# starfox.net
KiCad netlist of a schematic drawn in EAGLE
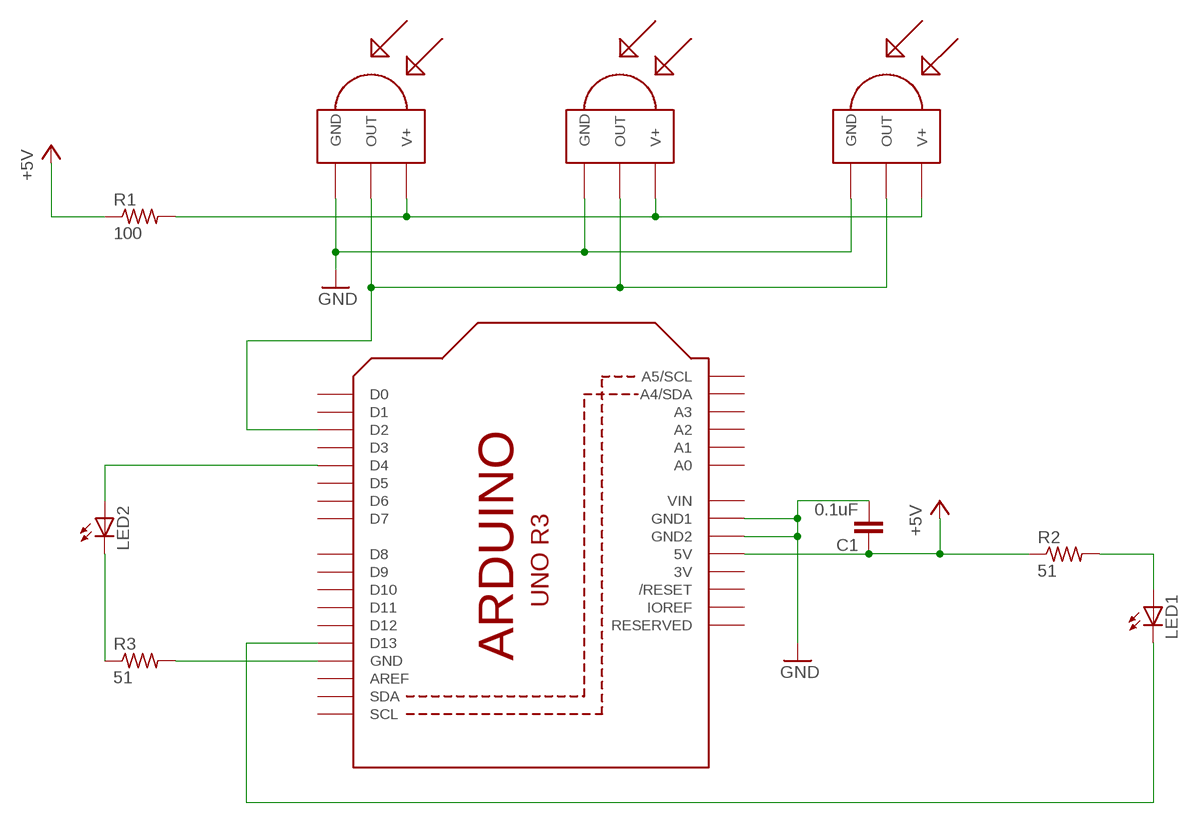
[diagram p0: schematic, sheet 1]

(export (version "E")
  (design (tool "Eeschema 10.0.6"))
  (components
    (comp (ref "C1")
      (value "0.1uF")
      (footprint "eagle-import:C025-025X050")
      (libsource (lib "eagle-import") (part "C-EU025-025X050"))
    )
    (comp (ref "LED1")
      (value "LED5MM")
      (footprint "eagle-import:LED5MM")
      (libsource (lib "eagle-import") (part "LED5MM"))
    )
    (comp (ref "LED2")
      (value "LED5MM")
      (footprint "eagle-import:LED5MM")
      (libsource (lib "eagle-import") (part "LED5MM"))
    )
    (comp (ref "R1")
      (value "100")
      (footprint "eagle-import:0204_7")
      (libsource (lib "eagle-import") (part "R-US_0204/7"))
    )
    (comp (ref "R2")
      (value "51")
      (footprint "eagle-import:0204_7")
      (libsource (lib "eagle-import") (part "R-US_0204/7"))
    )
    (comp (ref "R3")
      (value "51")
      (footprint "eagle-import:0204_7")
      (libsource (lib "eagle-import") (part "R-US_0204/7"))
    )
    (comp (ref "U$1")
      (value "TSOP4836")
      (footprint "eagle-import:TSOP18XX")
      (libsource (lib "eagle-import") (part "TSOP4836"))
    )
    (comp (ref "U$2")
      (value "TSOP4836")
      (footprint "eagle-import:TSOP18XX")
      (libsource (lib "eagle-import") (part "TSOP4836"))
    )
    (comp (ref "U$3")
      (value "TSOP4836")
      (footprint "eagle-import:TSOP18XX")
      (libsource (lib "eagle-import") (part "TSOP4836"))
    )
    (comp (ref "U1")
      (value "ARDUINOR3-DIMENSION")
      (footprint "eagle-import:ARDUINOR3")
      (libsource (lib "eagle-import") (part "ARDUINOR3-DIMENSION"))
    )
  )
  (nets
    (net (code "1") (name "+5V") (class "Default")
      (node (ref "C1") (pin "1") (pinfunction "1_1") (pintype "passive"))
      (node (ref "R1") (pin "1") (pinfunction "1_1") (pintype "passive"))
      (node (ref "R2") (pin "1") (pinfunction "1_1") (pintype "passive"))
      (node (ref "U1") (pin "5V") (pinfunction "5V_5V") (pintype "power_in"))
    )
    (net (code "2") (name "/3V") (class "Default")
      (node (ref "U1") (pin "3V") (pinfunction "3V_3V") (pintype "power_in"))
    )
    (net (code "3") (name "/VIN") (class "Default")
      (node (ref "U1") (pin "VIN") (pinfunction "VIN_VIN") (pintype "power_in"))
    )
    (net (code "4") (name "GND") (class "Default")
      (node (ref "C1") (pin "2") (pinfunction "2_2") (pintype "passive"))
      (node (ref "U$1") (pin "GND") (pinfunction "GND_GND") (pintype "bidirectional"))
      (node (ref "U$2") (pin "GND") (pinfunction "GND_GND") (pintype "bidirectional"))
      (node (ref "U$3") (pin "GND") (pinfunction "GND_GND") (pintype "bidirectional"))
      (node (ref "U1") (pin "GND1") (pinfunction "GND1_GND1") (pintype "power_in"))
      (node (ref "U1") (pin "GND2") (pinfunction "GND2_GND2") (pintype "power_in"))
    )
    (net (code "5") (name "Net-(LED1-C)") (class "Default")
      (node (ref "LED1") (pin "K") (pinfunction "C_K") (pintype "passive"))
      (node (ref "U1") (pin "D13") (pinfunction "D13_D13") (pintype "bidirectional"))
    )
    (net (code "6") (name "Net-(LED1-PadA)") (class "Default")
      (node (ref "LED1") (pin "A") (pinfunction "A_A") (pintype "passive"))
      (node (ref "R2") (pin "2") (pinfunction "2_2") (pintype "passive"))
    )
    (net (code "7") (name "Net-(LED2-C)") (class "Default")
      (node (ref "LED2") (pin "K") (pinfunction "C_K") (pintype "passive"))
      (node (ref "R3") (pin "1") (pinfunction "1_1") (pintype "passive"))
    )
    (net (code "8") (name "Net-(LED2-PadA)") (class "Default")
      (node (ref "LED2") (pin "A") (pinfunction "A_A") (pintype "passive"))
      (node (ref "U1") (pin "D4") (pinfunction "D4_D4") (pintype "bidirectional"))
    )
    (net (code "9") (name "Net-(R3-Pad2)") (class "Default")
      (node (ref "R3") (pin "2") (pinfunction "2_2") (pintype "passive"))
      (node (ref "U1") (pin "GND") (pinfunction "GND_GND") (pintype "power_in"))
    )
    (net (code "10") (name "Net-(U$1-PadOUT)") (class "Default")
      (node (ref "U$1") (pin "OUT") (pinfunction "OUT_OUT") (pintype "bidirectional"))
      (node (ref "U$2") (pin "OUT") (pinfunction "OUT_OUT") (pintype "bidirectional"))
      (node (ref "U$3") (pin "OUT") (pinfunction "OUT_OUT") (pintype "bidirectional"))
      (node (ref "U1") (pin "D2") (pinfunction "D2_D2") (pintype "bidirectional"))
    )
    (net (code "11") (name "Net-(U$1-V+)") (class "Default")
      (node (ref "R1") (pin "2") (pinfunction "2_2") (pintype "passive"))
      (node (ref "U$1") (pin "VCC") (pinfunction "V+_VCC") (pintype "bidirectional"))
      (node (ref "U$2") (pin "VCC") (pinfunction "V+_VCC") (pintype "bidirectional"))
      (node (ref "U$3") (pin "VCC") (pinfunction "V+_VCC") (pintype "bidirectional"))
    )
    (net (code "12") (name "unconnected-(U1-A4{slash}SDA-PadA4)") (class "Default")
      (node (ref "U1") (pin "A4") (pinfunction "A4/SDA_A4") (pintype "bidirectional"))
    )
    (net (code "13") (name "unconnected-(U1-A5{slash}SCL-PadA5)") (class "Default")
      (node (ref "U1") (pin "A5") (pinfunction "A5/SCL_A5") (pintype "bidirectional"))
    )
    (net (code "14") (name "unconnected-(U1-PadA0)") (class "Default")
      (node (ref "U1") (pin "A0") (pinfunction "A0_A0") (pintype "bidirectional"))
    )
    (net (code "15") (name "unconnected-(U1-PadA1)") (class "Default")
      (node (ref "U1") (pin "A1") (pinfunction "A1_A1") (pintype "bidirectional"))
    )
    (net (code "16") (name "unconnected-(U1-PadA2)") (class "Default")
      (node (ref "U1") (pin "A2") (pinfunction "A2_A2") (pintype "bidirectional"))
    )
    (net (code "17") (name "unconnected-(U1-PadA3)") (class "Default")
      (node (ref "U1") (pin "A3") (pinfunction "A3_A3") (pintype "bidirectional"))
    )
    (net (code "18") (name "unconnected-(U1-PadAREF)") (class "Default")
      (node (ref "U1") (pin "AREF") (pinfunction "AREF_AREF") (pintype "bidirectional"))
    )
    (net (code "19") (name "unconnected-(U1-PadD0)") (class "Default")
      (node (ref "U1") (pin "D0") (pinfunction "D0_D0") (pintype "bidirectional"))
    )
    (net (code "20") (name "unconnected-(U1-PadD1)") (class "Default")
      (node (ref "U1") (pin "D1") (pinfunction "D1_D1") (pintype "bidirectional"))
    )
    (net (code "21") (name "unconnected-(U1-PadD3)") (class "Default")
      (node (ref "U1") (pin "D3") (pinfunction "D3_D3") (pintype "bidirectional"))
    )
    (net (code "22") (name "unconnected-(U1-PadD5)") (class "Default")
      (node (ref "U1") (pin "D5") (pinfunction "D5_D5") (pintype "bidirectional"))
    )
    (net (code "23") (name "unconnected-(U1-PadD6)") (class "Default")
      (node (ref "U1") (pin "D6") (pinfunction "D6_D6") (pintype "bidirectional"))
    )
    (net (code "24") (name "unconnected-(U1-PadD7)") (class "Default")
      (node (ref "U1") (pin "D7") (pinfunction "D7_D7") (pintype "bidirectional"))
    )
    (net (code "25") (name "unconnected-(U1-PadD8)") (class "Default")
      (node (ref "U1") (pin "D8") (pinfunction "D8_D8") (pintype "bidirectional"))
    )
    (net (code "26") (name "unconnected-(U1-PadD9)") (class "Default")
      (node (ref "U1") (pin "D9") (pinfunction "D9_D9") (pintype "bidirectional"))
    )
    (net (code "27") (name "unconnected-(U1-PadD10)") (class "Default")
      (node (ref "U1") (pin "D10") (pinfunction "D10_D10") (pintype "bidirectional"))
    )
    (net (code "28") (name "unconnected-(U1-PadD11)") (class "Default")
      (node (ref "U1") (pin "D11") (pinfunction "D11_D11") (pintype "bidirectional"))
    )
    (net (code "29") (name "unconnected-(U1-PadD12)") (class "Default")
      (node (ref "U1") (pin "D12") (pinfunction "D12_D12") (pintype "bidirectional"))
    )
    (net (code "30") (name "unconnected-(U1-PadIOREF)") (class "Default")
      (node (ref "U1") (pin "IOREF") (pinfunction "IOREF_IOREF") (pintype "output"))
    )
    (net (code "31") (name "unconnected-(U1-PadRESERVED)") (class "Default")
      (node (ref "U1") (pin "RESERVED") (pinfunction "RESERVED_RESERVED") (pintype "no_connect"))
    )
    (net (code "32") (name "unconnected-(U1-PadSCL)") (class "Default")
      (node (ref "U1") (pin "SCL") (pinfunction "SCL_SCL") (pintype "bidirectional"))
    )
    (net (code "33") (name "unconnected-(U1-PadSDA)") (class "Default")
      (node (ref "U1") (pin "SDA") (pinfunction "SDA_SDA") (pintype "bidirectional"))
    )
    (net (code "34") (name "unconnected-(U1-{slash}RESET-PadRESET)") (class "Default")
      (node (ref "U1") (pin "RESET") (pinfunction "/RESET_RESET") (pintype "bidirectional"))
    )
  )
)
